# EbookReader_Schematic_11042025_v1.net
KiCad netlist of a schematic drawn in EAGLE
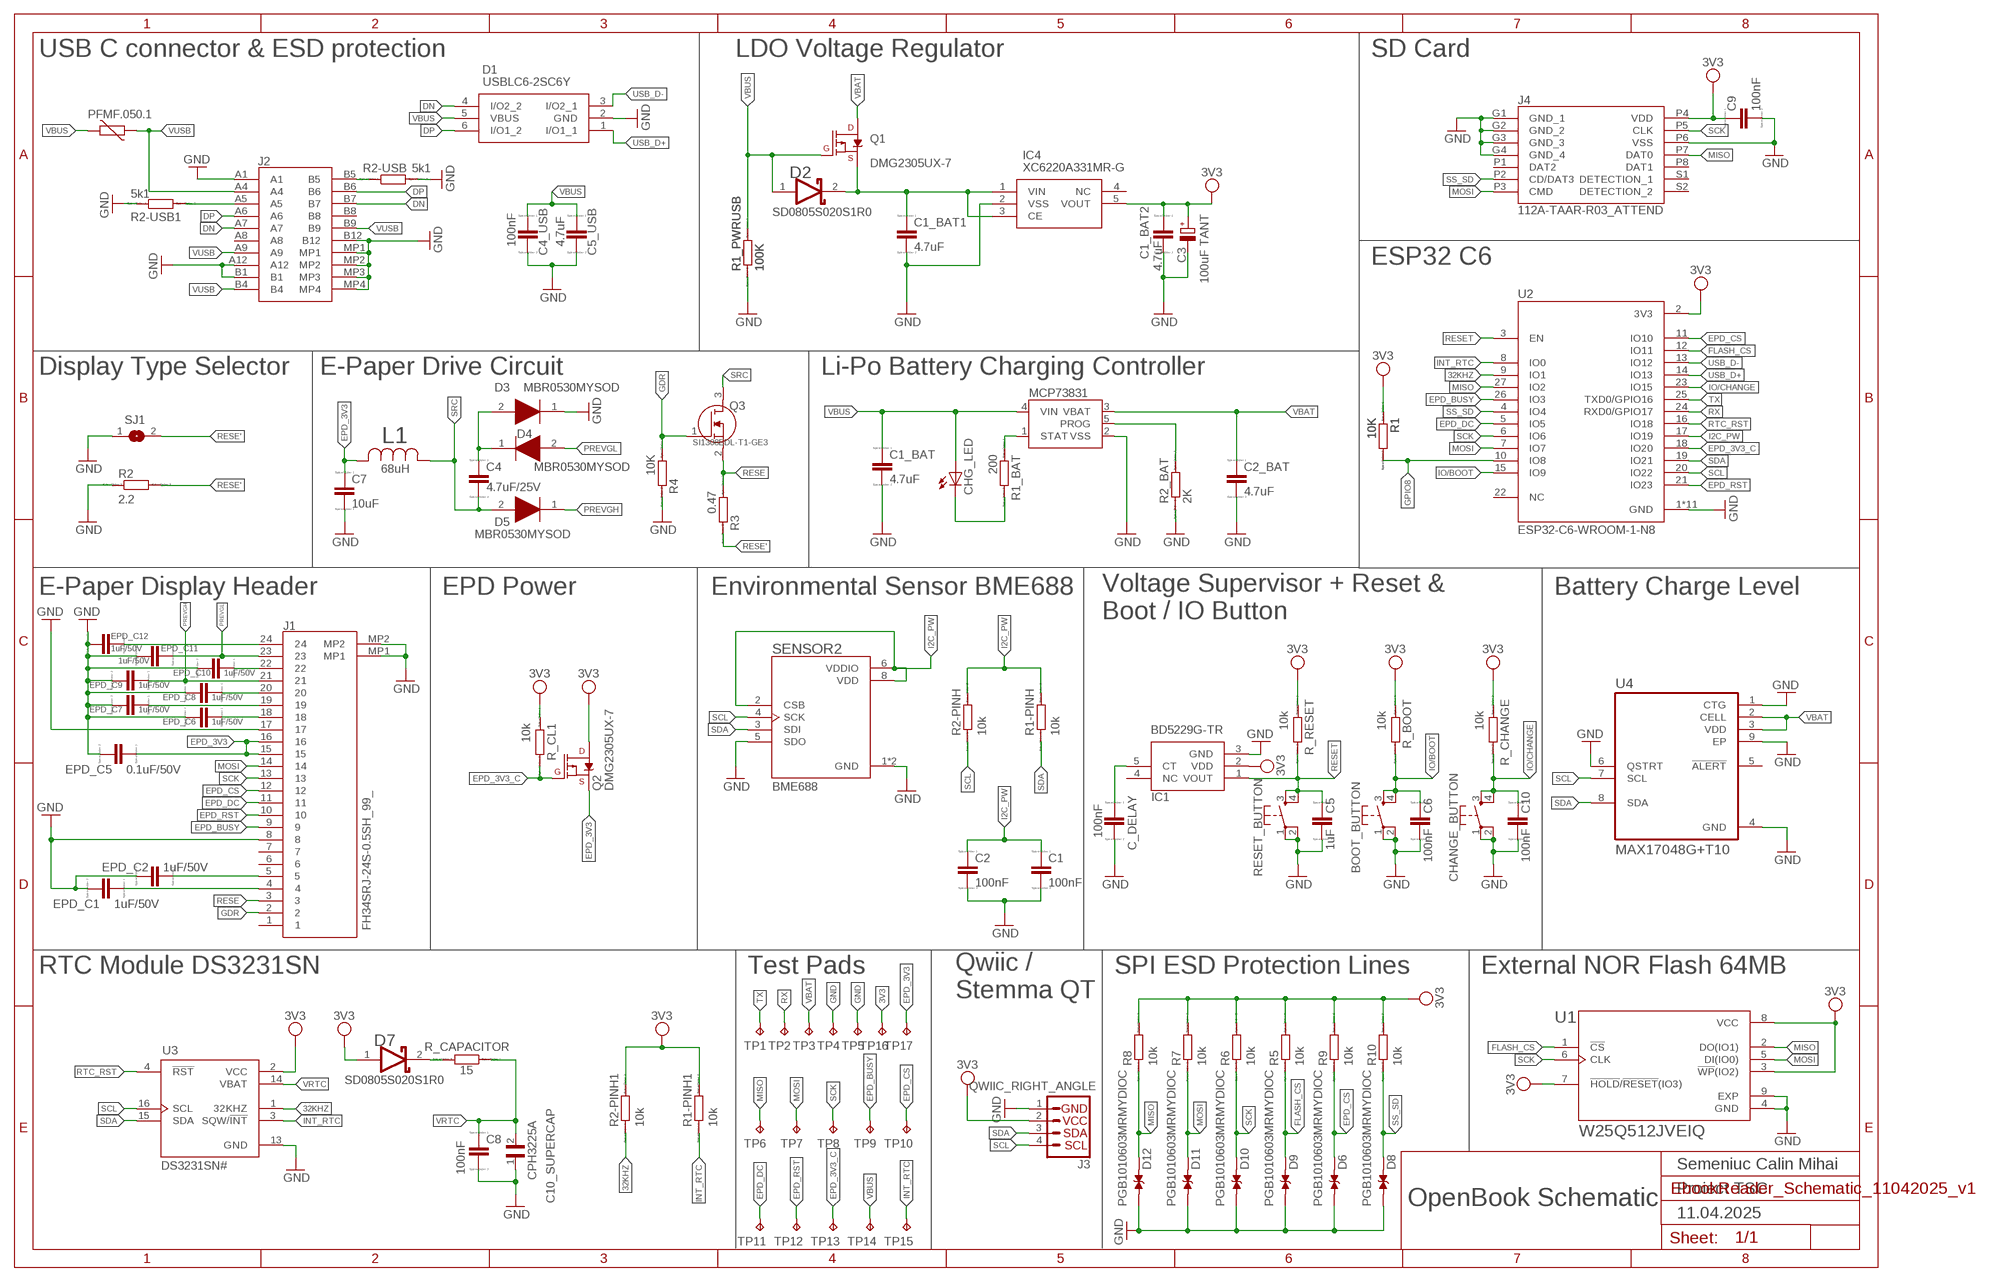
[diagram p0: schematic, sheet 1]

(export (version "E")
  (design (tool "Eeschema 10.0.6"))
  (components
    (comp (ref "BOOT_BUTTON")
      (value "BUTTON_CUSYOMV1FINAL_BUTT")
      (footprint "eagle-import:MYBUTTON")
      (libsource (lib "eagle-import") (part "BUTTON_CUSYOMV1FINAL_BUTT"))
    )
    (comp (ref "C1")
      (value "100nF")
      (footprint "eagle-import:EAGLE-LTSPICE_C0402")
      (libsource (lib "eagle-import") (part "ESP32_WROVER_EAGLE-LTSPICE_C"))
    )
    (comp (ref "C1_BAT")
      (value "4.7uF")
      (footprint "eagle-import:EAGLE-LTSPICE_C0402")
      (libsource (lib "eagle-import") (part "ESP32_WROVER_EAGLE-LTSPICE_C"))
    )
    (comp (ref "C1_BAT1")
      (value "4.7uF")
      (footprint "eagle-import:EAGLE-LTSPICE_C0402")
      (libsource (lib "eagle-import") (part "ESP32_WROVER_EAGLE-LTSPICE_C"))
    )
    (comp (ref "C1_BAT2")
      (value "4.7uF")
      (footprint "eagle-import:EAGLE-LTSPICE_C0402")
      (libsource (lib "eagle-import") (part "ESP32_WROVER_EAGLE-LTSPICE_C"))
    )
    (comp (ref "C2")
      (value "100nF")
      (footprint "eagle-import:EAGLE-LTSPICE_C0402")
      (libsource (lib "eagle-import") (part "ESP32_WROVER_EAGLE-LTSPICE_C"))
    )
    (comp (ref "C2_BAT")
      (value "4.7uF")
      (footprint "eagle-import:EAGLE-LTSPICE_C0402")
      (libsource (lib "eagle-import") (part "ESP32_WROVER_EAGLE-LTSPICE_C"))
    )
    (comp (ref "C3")
      (value "100uF TANT")
      (footprint "eagle-import:RCL_CT3528")
      (libsource (lib "eagle-import") (part "RCL_CPOL-EUCT3528"))
    )
    (comp (ref "C4")
      (value "4.7uF/25V")
      (footprint "eagle-import:EAGLE-LTSPICE_C0402")
      (libsource (lib "eagle-import") (part "ESP32_WROVER_EAGLE-LTSPICE_C"))
    )
    (comp (ref "C4_USB")
      (value "100nF")
      (footprint "eagle-import:EAGLE-LTSPICE_C0402")
      (libsource (lib "eagle-import") (part "ESP32_WROVER_EAGLE-LTSPICE_C"))
    )
    (comp (ref "C5")
      (value "1uF")
      (footprint "eagle-import:EAGLE-LTSPICE_C0402")
      (libsource (lib "eagle-import") (part "ESP32_WROVER_EAGLE-LTSPICE_C"))
    )
    (comp (ref "C5_USB")
      (value "4.7uF")
      (footprint "eagle-import:EAGLE-LTSPICE_C0402")
      (libsource (lib "eagle-import") (part "ESP32_WROVER_EAGLE-LTSPICE_C"))
    )
    (comp (ref "C6")
      (value "100nF")
      (footprint "eagle-import:EAGLE-LTSPICE_C0402")
      (libsource (lib "eagle-import") (part "ESP32_WROVER_EAGLE-LTSPICE_C"))
    )
    (comp (ref "C7")
      (value "10uF")
      (footprint "eagle-import:EAGLE-LTSPICE_C0402")
      (libsource (lib "eagle-import") (part "ESP32_WROVER_EAGLE-LTSPICE_C"))
    )
    (comp (ref "C8")
      (value "100nF")
      (footprint "eagle-import:EAGLE-LTSPICE_C0402")
      (libsource (lib "eagle-import") (part "ESP32_WROVER_EAGLE-LTSPICE_C"))
    )
    (comp (ref "C9")
      (value "100nF")
      (footprint "eagle-import:EAGLE-LTSPICE_C0402")
      (libsource (lib "eagle-import") (part "ESP32_WROVER_EAGLE-LTSPICE_C"))
    )
    (comp (ref "C10")
      (value "100nF")
      (footprint "eagle-import:EAGLE-LTSPICE_C0402")
      (libsource (lib "eagle-import") (part "ESP32_WROVER_EAGLE-LTSPICE_C"))
    )
    (comp (ref "C10_SUPERCAP")
      (value "CPH3225A")
      (footprint "eagle-import:CAPCP3225X100N")
      (fields (field (name "MF") "Seiko Instruments"))
      (libsource (lib "eagle-import") (part "CPH3225A"))
    )
    (comp (ref "CHANGE_BUTTON")
      (value "BUTTON_CUSYOMV1FINAL_BUTT")
      (footprint "eagle-import:MYBUTTON")
      (libsource (lib "eagle-import") (part "BUTTON_CUSYOMV1FINAL_BUTT"))
    )
    (comp (ref "CHG_LED")
      (value "ADAFRUIT_LEDCHIP-LED0603")
      (footprint "eagle-import:ADAFRUIT_CHIP-LED0603")
      (libsource (lib "eagle-import") (part "ADAFRUIT_LEDCHIP-LED0603"))
    )
    (comp (ref "C_DELAY")
      (value "100nF")
      (footprint "eagle-import:EAGLE-LTSPICE_C0402")
      (libsource (lib "eagle-import") (part "ESP32_WROVER_EAGLE-LTSPICE_C"))
    )
    (comp (ref "D1")
      (value "USBLC6-2SC6Y")
      (footprint "eagle-import:SOT95P280X145-6N")
      (fields (field (name "MF") "STMicroelectronics"))
      (libsource (lib "eagle-import") (part "USBLC6-2SC6Y"))
    )
    (comp (ref "D2")
      (value "ESP32_WROVER_AVX---SD0805S020S1R0_AVX_SD0805S020S1R0_0_0")
      (footprint "eagle-import:ESP32_WROVER_AVX---SD0805S020S1R0_AVX_SD0805S020S1R0_0")
      (fields (field (name "FOOPRINT") "SD0805S020S1R0"))
      (libsource (lib "eagle-import") (part "ESP32_WROVER_AVX---SD0805S020S1R0_AVX_SD0805S020S1R0_0_0"))
    )
    (comp (ref "D3")
      (value "MBR0530MYSOD")
      (footprint "eagle-import:SOD3716X135N")
      (libsource (lib "eagle-import") (part "MBR0530MYSOD"))
    )
    (comp (ref "D4")
      (value "MBR0530MYSOD")
      (footprint "eagle-import:SOD3716X135N")
      (libsource (lib "eagle-import") (part "MBR0530MYSOD"))
    )
    (comp (ref "D5")
      (value "MBR0530MYSOD")
      (footprint "eagle-import:SOD3716X135N")
      (libsource (lib "eagle-import") (part "MBR0530MYSOD"))
    )
    (comp (ref "D6")
      (value "PGB1010603MRMYDIOC")
      (footprint "eagle-import:DIOC1608X36N")
      (libsource (lib "eagle-import") (part "PGB1010603MRMYDIOC"))
    )
    (comp (ref "D7")
      (value "ESP32_WROVER_AVX---SD0805S020S1R0_AVX_SD0805S020S1R0_0_0")
      (footprint "eagle-import:ESP32_WROVER_AVX---SD0805S020S1R0_AVX_SD0805S020S1R0_0")
      (fields (field (name "FOOPRINT") "SD0805S020S1R0"))
      (libsource (lib "eagle-import") (part "ESP32_WROVER_AVX---SD0805S020S1R0_AVX_SD0805S020S1R0_0_0"))
    )
    (comp (ref "D8")
      (value "PGB1010603MRMYDIOC")
      (footprint "eagle-import:DIOC1608X36N")
      (libsource (lib "eagle-import") (part "PGB1010603MRMYDIOC"))
    )
    (comp (ref "D9")
      (value "PGB1010603MRMYDIOC")
      (footprint "eagle-import:DIOC1608X36N")
      (libsource (lib "eagle-import") (part "PGB1010603MRMYDIOC"))
    )
    (comp (ref "D10")
      (value "PGB1010603MRMYDIOC")
      (footprint "eagle-import:DIOC1608X36N")
      (libsource (lib "eagle-import") (part "PGB1010603MRMYDIOC"))
    )
    (comp (ref "D11")
      (value "PGB1010603MRMYDIOC")
      (footprint "eagle-import:DIOC1608X36N")
      (libsource (lib "eagle-import") (part "PGB1010603MRMYDIOC"))
    )
    (comp (ref "D12")
      (value "PGB1010603MRMYDIOC")
      (footprint "eagle-import:DIOC1608X36N")
      (libsource (lib "eagle-import") (part "PGB1010603MRMYDIOC"))
    )
    (comp (ref "EPD_C1")
      (value "1uF/50V")
      (footprint "eagle-import:EAGLE-LTSPICE_C0402")
      (libsource (lib "eagle-import") (part "ESP32_WROVER_EAGLE-LTSPICE_C"))
    )
    (comp (ref "EPD_C2")
      (value "1uF/50V")
      (footprint "eagle-import:EAGLE-LTSPICE_C0402")
      (libsource (lib "eagle-import") (part "ESP32_WROVER_EAGLE-LTSPICE_C"))
    )
    (comp (ref "EPD_C5")
      (value "0.1uF/50V")
      (footprint "eagle-import:EAGLE-LTSPICE_C0402")
      (libsource (lib "eagle-import") (part "ESP32_WROVER_EAGLE-LTSPICE_C"))
    )
    (comp (ref "EPD_C6")
      (value "1uF/50V")
      (footprint "eagle-import:EAGLE-LTSPICE_C0402")
      (libsource (lib "eagle-import") (part "ESP32_WROVER_EAGLE-LTSPICE_C"))
    )
    (comp (ref "EPD_C7")
      (value "1uF/50V")
      (footprint "eagle-import:EAGLE-LTSPICE_C0402")
      (libsource (lib "eagle-import") (part "ESP32_WROVER_EAGLE-LTSPICE_C"))
    )
    (comp (ref "EPD_C8")
      (value "1uF/50V")
      (footprint "eagle-import:EAGLE-LTSPICE_C0402")
      (libsource (lib "eagle-import") (part "ESP32_WROVER_EAGLE-LTSPICE_C"))
    )
    (comp (ref "EPD_C9")
      (value "1uF/50V")
      (footprint "eagle-import:EAGLE-LTSPICE_C0402")
      (libsource (lib "eagle-import") (part "ESP32_WROVER_EAGLE-LTSPICE_C"))
    )
    (comp (ref "EPD_C10")
      (value "1uF/50V")
      (footprint "eagle-import:EAGLE-LTSPICE_C0402")
      (libsource (lib "eagle-import") (part "ESP32_WROVER_EAGLE-LTSPICE_C"))
    )
    (comp (ref "EPD_C11")
      (value "1uF/50V")
      (footprint "eagle-import:EAGLE-LTSPICE_C0402")
      (libsource (lib "eagle-import") (part "ESP32_WROVER_EAGLE-LTSPICE_C"))
    )
    (comp (ref "EPD_C12")
      (value "1uF/50V")
      (footprint "eagle-import:EAGLE-LTSPICE_C0402")
      (libsource (lib "eagle-import") (part "ESP32_WROVER_EAGLE-LTSPICE_C"))
    )
    (comp (ref "IC1")
      (value "BD5229G-TR")
      (footprint "eagle-import:SOT95P280X125-5N")
      (fields (field (name "MOUSER_PART_NUMBER") "755-BD5229G-TR"))
      (libsource (lib "eagle-import") (part "BD5229G-TR"))
    )
    (comp (ref "IC4")
      (value "XC6220A331MR-G")
      (footprint "eagle-import:SOT95P280X120-5N")
      (fields (field (name "MOUSER_PART_NUMBER") "865-XC6220A331MR-G"))
      (libsource (lib "eagle-import") (part "XC6220A331MR-G"))
    )
    (comp (ref "J1")
      (value "FH34SRJ-24S-0.5SH_99_")
      (footprint "eagle-import:FH34SRJ24S05SH99")
      (fields
        (field (name "MANUFACTURER_PART_NUMBER") "FH34SRJ-24S-0.5SH(99)")
        (field (name "MOUSER_PART_NUMBER") "798-FH34SRJ24S05SH99")
      )
      (libsource (lib "eagle-import") (part "FH34SRJ-24S-0.5SH_99_"))
    )
    (comp (ref "J2")
      (value "SAMACSYS_PARTS_USB4110-GF-A")
      (footprint "eagle-import:SAMACSYS_PARTS_USB4110GFA")
      (fields
        (field (name "MANUFACTURER_PART_NUMBER") "USB4110-GF-A")
        (field (name "MOUSER_PART_NUMBER") "640-USB4110-GF-A")
      )
      (libsource (lib "eagle-import") (part "SAMACSYS_PARTS_USB4110-GF-A"))
    )
    (comp (ref "J3")
      (value "QWIIC_RIGHT_ANGLE")
      (footprint "eagle-import:JST04_1MM_RA")
      (libsource (lib "eagle-import") (part "QWIIC_CONNECTORJS-1MM"))
    )
    (comp (ref "J4")
      (value "112A-TAAR-R03_ATTEND")
      (footprint "eagle-import:112ATAARR03ATTEND")
      (fields (field (name "MANUFACTURER_PART_NUMBER") "112A-TAAR-R03 ATTEND"))
      (libsource (lib "eagle-import") (part "112A-TAAR-R03_ATTEND"))
    )
    (comp (ref "L1")
      (value "744043680IND_4828-WE-TPC_WRE")
      (footprint "eagle-import:IND_4828-WE-TPC_WRE")
      (fields
        (field (name "MANUFACTURER_PART_NUMBER") "744043680")
        (field (name "VAL") "68uH")
        (field (name "COPYRIGHT") "Copyright (C) 2024 Ultra Librarian. All rights reserved.")
      )
      (libsource (lib "eagle-import") (part "744043680IND_4828-WE-TPC_WRE"))
    )
    (comp (ref "MCP73831")
      (value "ESP32_WROVER_SPARKFUN-IC-POWER_MCP73831")
      (footprint "eagle-import:ESP32_WROVER_SPARKFUN-IC-POWER_SOT23-5")
      (libsource (lib "eagle-import") (part "ESP32_WROVER_SPARKFUN-IC-POWER_MCP73831"))
    )
    (comp (ref "PFMF.050.1")
      (value "ESP32C6_VARISTORCN1812")
      (footprint "eagle-import:ESP32C6_VARISTOR_CT_CN1812")
      (libsource (lib "eagle-import") (part "ESP32C6_VARISTORCN1812"))
    )
    (comp (ref "Q1")
      (value "20V/4.2A/52mΩ/1.4W")
      (footprint "DMG2305UX-7")
      (libsource (lib "eagle-import") (part "ESP32_WROVER_SPARKFUN-DISCRETESEMI_MOSFET_PCH"))
    )
    (comp (ref "Q2")
      (value "20V/4.2A/52mΩ/1.4W")
      (footprint "DMG2305UX-7")
      (libsource (lib "eagle-import") (part "ESP32_WROVER_SPARKFUN-DISCRETESEMI_MOSFET_PCH"))
    )
    (comp (ref "Q3")
      (value "SI1308EDL-T1-GE3")
      (footprint "eagle-import:SOT65P210X110-3N")
      (fields (field (name "MF") "Vishay Siliconix"))
      (libsource (lib "eagle-import") (part "SI1308EDL-T1-GE3"))
    )
    (comp (ref "R1")
      (value "10K")
      (footprint "eagle-import:ESP32_WROVER_EAGLE-LTSPICE_R0402")
      (libsource (lib "eagle-import") (part "ESP32_WROVER_EAGLE-LTSPICE_R"))
    )
    (comp (ref "R1-PINH")
      (value "10k")
      (footprint "eagle-import:ESP32_WROVER_EAGLE-LTSPICE_R0402")
      (libsource (lib "eagle-import") (part "ESP32_WROVER_EAGLE-LTSPICE_R"))
    )
    (comp (ref "R1-PINH1")
      (value "10k")
      (footprint "eagle-import:ESP32_WROVER_EAGLE-LTSPICE_R0402")
      (libsource (lib "eagle-import") (part "ESP32_WROVER_EAGLE-LTSPICE_R"))
    )
    (comp (ref "R1_BAT")
      (value "200")
      (footprint "eagle-import:ESP32_WROVER_EAGLE-LTSPICE_R0402")
      (libsource (lib "eagle-import") (part "ESP32_WROVER_EAGLE-LTSPICE_R"))
    )
    (comp (ref "R1_PWRUSB")
      (value "100K")
      (footprint "eagle-import:ESP32_WROVER_EAGLE-LTSPICE_R0402")
      (libsource (lib "eagle-import") (part "ESP32_WROVER_EAGLE-LTSPICE_R"))
    )
    (comp (ref "R2")
      (value "2.2")
      (footprint "eagle-import:ESP32_WROVER_EAGLE-LTSPICE_R0402")
      (libsource (lib "eagle-import") (part "ESP32_WROVER_EAGLE-LTSPICE_R"))
    )
    (comp (ref "R2-PINH")
      (value "10k")
      (footprint "eagle-import:ESP32_WROVER_EAGLE-LTSPICE_R0402")
      (libsource (lib "eagle-import") (part "ESP32_WROVER_EAGLE-LTSPICE_R"))
    )
    (comp (ref "R2-PINH1")
      (value "10k")
      (footprint "eagle-import:ESP32_WROVER_EAGLE-LTSPICE_R0402")
      (libsource (lib "eagle-import") (part "ESP32_WROVER_EAGLE-LTSPICE_R"))
    )
    (comp (ref "R2-USB")
      (value "5k1")
      (footprint "eagle-import:ESP32_WROVER_EAGLE-LTSPICE_R0402")
      (libsource (lib "eagle-import") (part "ESP32_WROVER_EAGLE-LTSPICE_R"))
    )
    (comp (ref "R2-USB1")
      (value "5k1")
      (footprint "eagle-import:ESP32_WROVER_EAGLE-LTSPICE_R0402")
      (libsource (lib "eagle-import") (part "ESP32_WROVER_EAGLE-LTSPICE_R"))
    )
    (comp (ref "R2_BAT")
      (value "2K")
      (footprint "eagle-import:ESP32_WROVER_EAGLE-LTSPICE_R0402")
      (libsource (lib "eagle-import") (part "ESP32_WROVER_EAGLE-LTSPICE_R"))
    )
    (comp (ref "R3")
      (value "0.47")
      (footprint "eagle-import:ESP32_WROVER_EAGLE-LTSPICE_R0402")
      (libsource (lib "eagle-import") (part "ESP32_WROVER_EAGLE-LTSPICE_R"))
    )
    (comp (ref "R4")
      (value "10K")
      (footprint "eagle-import:ESP32_WROVER_EAGLE-LTSPICE_R0402")
      (libsource (lib "eagle-import") (part "ESP32_WROVER_EAGLE-LTSPICE_R"))
    )
    (comp (ref "R5")
      (value "10k")
      (footprint "eagle-import:ESP32_WROVER_EAGLE-LTSPICE_R0402")
      (libsource (lib "eagle-import") (part "ESP32_WROVER_EAGLE-LTSPICE_R"))
    )
    (comp (ref "R6")
      (value "10k")
      (footprint "eagle-import:ESP32_WROVER_EAGLE-LTSPICE_R0402")
      (libsource (lib "eagle-import") (part "ESP32_WROVER_EAGLE-LTSPICE_R"))
    )
    (comp (ref "R7")
      (value "10k")
      (footprint "eagle-import:ESP32_WROVER_EAGLE-LTSPICE_R0402")
      (libsource (lib "eagle-import") (part "ESP32_WROVER_EAGLE-LTSPICE_R"))
    )
    (comp (ref "R8")
      (value "10k")
      (footprint "eagle-import:ESP32_WROVER_EAGLE-LTSPICE_R0402")
      (libsource (lib "eagle-import") (part "ESP32_WROVER_EAGLE-LTSPICE_R"))
    )
    (comp (ref "R9")
      (value "10k")
      (footprint "eagle-import:ESP32_WROVER_EAGLE-LTSPICE_R0402")
      (libsource (lib "eagle-import") (part "ESP32_WROVER_EAGLE-LTSPICE_R"))
    )
    (comp (ref "R10")
      (value "10k")
      (footprint "eagle-import:ESP32_WROVER_EAGLE-LTSPICE_R0402")
      (libsource (lib "eagle-import") (part "ESP32_WROVER_EAGLE-LTSPICE_R"))
    )
    (comp (ref "RESET_BUTTON")
      (value "BUTTON_CUSYOMV1FINAL_BUTT")
      (footprint "eagle-import:MYBUTTON")
      (libsource (lib "eagle-import") (part "BUTTON_CUSYOMV1FINAL_BUTT"))
    )
    (comp (ref "R_BOOT")
      (value "10k")
      (footprint "eagle-import:ESP32_WROVER_EAGLE-LTSPICE_R0402")
      (libsource (lib "eagle-import") (part "ESP32_WROVER_EAGLE-LTSPICE_R"))
    )
    (comp (ref "R_CAPACITOR")
      (value "15")
      (footprint "eagle-import:ESP32_WROVER_EAGLE-LTSPICE_R0402")
      (libsource (lib "eagle-import") (part "ESP32_WROVER_EAGLE-LTSPICE_R"))
    )
    (comp (ref "R_CHANGE")
      (value "10k")
      (footprint "eagle-import:ESP32_WROVER_EAGLE-LTSPICE_R0402")
      (libsource (lib "eagle-import") (part "ESP32_WROVER_EAGLE-LTSPICE_R"))
    )
    (comp (ref "R_CL1")
      (value "10k")
      (footprint "eagle-import:ESP32_WROVER_EAGLE-LTSPICE_R0402")
      (libsource (lib "eagle-import") (part "ESP32_WROVER_EAGLE-LTSPICE_R"))
    )
    (comp (ref "R_RESET")
      (value "10k")
      (footprint "eagle-import:ESP32_WROVER_EAGLE-LTSPICE_R0402")
      (libsource (lib "eagle-import") (part "ESP32_WROVER_EAGLE-LTSPICE_R"))
    )
    (comp (ref "SENSOR2")
      (value "ESP32_WROVER_BME680_BME680")
      (footprint "BME688")
      (fields (field (name "MF") "Bosch Sensortec") (field (name "MP") "BME680"))
      (libsource (lib "eagle-import") (part "ESP32_WROVER_BME680_BME680"))
    )
    (comp (ref "SJ1") (value "SJ") (footprint "eagle-import:SJ") (libsource (lib "eagle-import") (part "SJ")))
    (comp (ref "TP1")
      (value "TP")
      (footprint "eagle-import:TP20R")
      (libsource (lib "eagle-import") (part "TP"))
    )
    (comp (ref "TP2")
      (value "TP")
      (footprint "eagle-import:TP20R")
      (libsource (lib "eagle-import") (part "TP"))
    )
    (comp (ref "TP3")
      (value "TP")
      (footprint "eagle-import:TP20R")
      (libsource (lib "eagle-import") (part "TP"))
    )
    (comp (ref "TP4")
      (value "TP")
      (footprint "eagle-import:TP20R")
      (libsource (lib "eagle-import") (part "TP"))
    )
    (comp (ref "TP5")
      (value "TP")
      (footprint "eagle-import:TP20R")
      (libsource (lib "eagle-import") (part "TP"))
    )
    (comp (ref "TP6")
      (value "TP")
      (footprint "eagle-import:TP20R")
      (libsource (lib "eagle-import") (part "TP"))
    )
    (comp (ref "TP7")
      (value "TP")
      (footprint "eagle-import:TP20R")
      (libsource (lib "eagle-import") (part "TP"))
    )
    (comp (ref "TP8")
      (value "TP")
      (footprint "eagle-import:TP20R")
      (libsource (lib "eagle-import") (part "TP"))
    )
    (comp (ref "TP9")
      (value "TP")
      (footprint "eagle-import:TP20R")
      (libsource (lib "eagle-import") (part "TP"))
    )
    (comp (ref "TP10")
      (value "TP")
      (footprint "eagle-import:TP20R")
      (libsource (lib "eagle-import") (part "TP"))
    )
    (comp (ref "TP11")
      (value "TP")
      (footprint "eagle-import:TP20R")
      (libsource (lib "eagle-import") (part "TP"))
    )
    (comp (ref "TP12")
      (value "TP")
      (footprint "eagle-import:TP20R")
      (libsource (lib "eagle-import") (part "TP"))
    )
    (comp (ref "TP13")
      (value "TP")
      (footprint "eagle-import:TP20R")
      (libsource (lib "eagle-import") (part "TP"))
    )
    (comp (ref "TP14")
      (value "TP")
      (footprint "eagle-import:TP20R")
      (libsource (lib "eagle-import") (part "TP"))
    )
    (comp (ref "TP15")
      (value "TP")
      (footprint "eagle-import:TP20R")
      (libsource (lib "eagle-import") (part "TP"))
    )
    (comp (ref "TP16")
      (value "TP")
      (footprint "eagle-import:TP20R")
      (libsource (lib "eagle-import") (part "TP"))
    )
    (comp (ref "TP17")
      (value "TP")
      (footprint "eagle-import:TP20R")
      (libsource (lib "eagle-import") (part "TP"))
    )
    (comp (ref "U1")
      (value "W25Q512JVEIQ")
      (footprint "eagle-import:SON127P600X800X80-9N")
      (fields (field (name "MF") "Winbond Electronics"))
      (libsource (lib "eagle-import") (part "W25Q512JVEIQ"))
    )
    (comp (ref "U2")
      (value "ESP32-C6-WROOM-1-N8")
      (footprint "eagle-import:XCVR_ESP32-C6-WROOM-1-N8")
      (fields (field (name "MF") "Espressif Systems"))
      (libsource (lib "eagle-import") (part "ESP32-C6-WROOM-1-N8"))
    )
    (comp (ref "U3")
      (value "DS3231SN#")
      (footprint "eagle-import:SOIC127P1032X265-16N")
      (fields (field (name "MF") "Analog Devices"))
      (libsource (lib "eagle-import") (part "DS3231SN#"))
    )
    (comp (ref "U4")
      (value "MAX17048G+T10")
      (footprint "eagle-import:SON50P200X200X80-9N")
      (fields (field (name "MF") "Analog Devices") (field (name "SPICEPREFIX") "X"))
      (libsource (lib "eagle-import") (part "MAX17048G+T10"))
    )
  )
  (nets
    (net (code "1") (name "3V3") (class "Default")
      (node (ref "C1_BAT2") (pin "1") (pinfunction "1_1") (pintype "passive"))
      (node (ref "C3") (pin "+") (pinfunction "+_+") (pintype "passive"))
      (node (ref "C9") (pin "1") (pinfunction "1_1") (pintype "passive"))
      (node (ref "D7") (pin "1") (pinfunction "ANODE_1") (pintype "bidirectional"))
      (node (ref "IC1") (pin "2") (pinfunction "VDD_2") (pintype "bidirectional"))
      (node (ref "IC4") (pin "5") (pinfunction "VOUT_5") (pintype "bidirectional"))
      (node (ref "J3") (pin "2") (pinfunction "2_2") (pintype "power_in"))
      (node (ref "J4") (pin "P4") (pinfunction "VDD_P4") (pintype "bidirectional"))
      (node (ref "Q2") (pin "1") (pinfunction "D_1") (pintype "bidirectional"))
      (node (ref "R1") (pin "1") (pinfunction "1_1") (pintype "passive"))
      (node (ref "R1-PINH1") (pin "2") (pinfunction "2_2") (pintype "passive"))
      (node (ref "R10") (pin "2") (pinfunction "2_2") (pintype "passive"))
      (node (ref "R2-PINH1") (pin "2") (pinfunction "2_2") (pintype "passive"))
      (node (ref "R5") (pin "2") (pinfunction "2_2") (pintype "passive"))
      (node (ref "R6") (pin "2") (pinfunction "2_2") (pintype "passive"))
      (node (ref "R7") (pin "2") (pinfunction "2_2") (pintype "passive"))
      (node (ref "R8") (pin "2") (pinfunction "2_2") (pintype "passive"))
      (node (ref "R9") (pin "2") (pinfunction "2_2") (pintype "passive"))
      (node (ref "R_BOOT") (pin "1") (pinfunction "1_1") (pintype "passive"))
      (node (ref "R_CHANGE") (pin "1") (pinfunction "1_1") (pintype "passive"))
      (node (ref "R_CL1") (pin "1") (pinfunction "1_1") (pintype "passive"))
      (node (ref "R_RESET") (pin "1") (pinfunction "1_1") (pintype "passive"))
      (node (ref "TP16") (pin "TP") (pinfunction "TP_TP") (pintype "input"))
      (node (ref "U1") (pin "3") (pinfunction "~{WP}(IO2)_3") (pintype "bidirectional"))
      (node (ref "U1") (pin "7") (pinfunction "~{HOLD}/~{RESET}(IO3)_7") (pintype "bidirectional"))
      (node (ref "U1") (pin "8") (pinfunction "VCC_8") (pintype "power_in"))
      (node (ref "U2") (pin "2") (pinfunction "3V3_2") (pintype "power_in"))
      (node (ref "U3") (pin "2") (pinfunction "VCC_2") (pintype "power_in"))
    )
    (net (code "2") (name "32KHZ") (class "Default")
      (node (ref "R2-PINH1") (pin "1") (pinfunction "1_1") (pintype "passive"))
      (node (ref "U2") (pin "9") (pinfunction "IO1_9") (pintype "bidirectional"))
      (node (ref "U3") (pin "1") (pinfunction "32KHZ_1") (pintype "output"))
    )
    (net (code "3") (name "DN") (class "Default")
      (node (ref "D1") (pin "4") (pinfunction "I/O2_2_4") (pintype "bidirectional"))
      (node (ref "J2") (pin "A7") (pinfunction "A7_A7") (pintype "bidirectional"))
      (node (ref "J2") (pin "B7") (pinfunction "B7_B7") (pintype "bidirectional"))
    )
    (net (code "4") (name "DP") (class "Default")
      (node (ref "D1") (pin "6") (pinfunction "I/O1_2_6") (pintype "bidirectional"))
      (node (ref "J2") (pin "A6") (pinfunction "A6_A6") (pintype "bidirectional"))
      (node (ref "J2") (pin "B6") (pinfunction "B6_B6") (pintype "bidirectional"))
    )
    (net (code "5") (name "EPD_3V3") (class "Default")
      (node (ref "C7") (pin "1") (pinfunction "1_1") (pintype "passive"))
      (node (ref "EPD_C5") (pin "1") (pinfunction "1_1") (pintype "passive"))
      (node (ref "J1") (pin "15") (pinfunction "15_15") (pintype "bidirectional"))
      (node (ref "J1") (pin "16") (pinfunction "16_16") (pintype "bidirectional"))
      (node (ref "L1") (pin "2") (pinfunction "2_2") (pintype "passive"))
      (node (ref "Q2") (pin "3") (pinfunction "S_3") (pintype "bidirectional"))
      (node (ref "TP17") (pin "TP") (pinfunction "TP_TP") (pintype "input"))
    )
    (net (code "6") (name "EPD_3V3_C") (class "Default")
      (node (ref "Q2") (pin "2") (pinfunction "G_2") (pintype "bidirectional"))
      (node (ref "R_CL1") (pin "2") (pinfunction "2_2") (pintype "passive"))
      (node (ref "TP13") (pin "TP") (pinfunction "TP_TP") (pintype "input"))
      (node (ref "U2") (pin "18") (pinfunction "IO20_18") (pintype "bidirectional"))
    )
    (net (code "7") (name "EPD_BUSY") (class "Default")
      (node (ref "J1") (pin "9") (pinfunction "9_9") (pintype "bidirectional"))
      (node (ref "TP9") (pin "TP") (pinfunction "TP_TP") (pintype "input"))
      (node (ref "U2") (pin "26") (pinfunction "IO3_26") (pintype "bidirectional"))
    )
    (net (code "8") (name "EPD_CS") (class "Default")
      (node (ref "D6") (pin "2") (pinfunction "2_2") (pintype "passive"))
      (node (ref "J1") (pin "12") (pinfunction "12_12") (pintype "bidirectional"))
      (node (ref "R9") (pin "1") (pinfunction "1_1") (pintype "passive"))
      (node (ref "TP10") (pin "TP") (pinfunction "TP_TP") (pintype "input"))
      (node (ref "U2") (pin "11") (pinfunction "IO10_11") (pintype "bidirectional"))
    )
    (net (code "9") (name "EPD_DC") (class "Default")
      (node (ref "J1") (pin "11") (pinfunction "11_11") (pintype "bidirectional"))
      (node (ref "TP11") (pin "TP") (pinfunction "TP_TP") (pintype "input"))
      (node (ref "U2") (pin "5") (pinfunction "IO5_5") (pintype "bidirectional"))
    )
    (net (code "10") (name "EPD_RST") (class "Default")
      (node (ref "J1") (pin "10") (pinfunction "10_10") (pintype "bidirectional"))
      (node (ref "TP12") (pin "TP") (pinfunction "TP_TP") (pintype "input"))
      (node (ref "U2") (pin "21") (pinfunction "IO23_21") (pintype "bidirectional"))
    )
    (net (code "11") (name "FLASH_CS") (class "Default")
      (node (ref "D9") (pin "2") (pinfunction "2_2") (pintype "passive"))
      (node (ref "R5") (pin "1") (pinfunction "1_1") (pintype "passive"))
      (node (ref "U1") (pin "1") (pinfunction "~{CS}_1") (pintype "input"))
      (node (ref "U2") (pin "12") (pinfunction "IO11_12") (pintype "bidirectional"))
    )
    (net (code "12") (name "GDR") (class "Default")
      (node (ref "J1") (pin "2") (pinfunction "2_2") (pintype "bidirectional"))
      (node (ref "Q3") (pin "1") (pinfunction "G_1") (pintype "bidirectional"))
      (node (ref "R4") (pin "1") (pinfunction "1_1") (pintype "passive"))
    )
    (net (code "13") (name "GND") (class "Default")
      (node (ref "BOOT_BUTTON") (pin "1") (pinfunction "1_1") (pintype "passive"))
      (node (ref "BOOT_BUTTON") (pin "2") (pinfunction "2_2") (pintype "passive"))
      (node (ref "C1") (pin "2") (pinfunction "2_2") (pintype "passive"))
      (node (ref "C10") (pin "2") (pinfunction "2_2") (pintype "passive"))
      (node (ref "C10_SUPERCAP") (pin "1") (pinfunction "1_1") (pintype "passive"))
      (node (ref "C1_BAT") (pin "2") (pinfunction "2_2") (pintype "passive"))
      (node (ref "C1_BAT1") (pin "2") (pinfunction "2_2") (pintype "passive"))
      (node (ref "C1_BAT2") (pin "2") (pinfunction "2_2") (pintype "passive"))
      (node (ref "C2") (pin "2") (pinfunction "2_2") (pintype "passive"))
      (node (ref "C2_BAT") (pin "2") (pinfunction "2_2") (pintype "passive"))
      (node (ref "C3") (pin "-") (pinfunction "-_-") (pintype "passive"))
      (node (ref "C4_USB") (pin "2") (pinfunction "2_2") (pintype "passive"))
      (node (ref "C5") (pin "2") (pinfunction "2_2") (pintype "passive"))
      (node (ref "C5_USB") (pin "2") (pinfunction "2_2") (pintype "passive"))
      (node (ref "C6") (pin "2") (pinfunction "2_2") (pintype "passive"))
      (node (ref "C7") (pin "2") (pinfunction "2_2") (pintype "passive"))
      (node (ref "C8") (pin "2") (pinfunction "2_2") (pintype "passive"))
      (node (ref "C9") (pin "2") (pinfunction "2_2") (pintype "passive"))
      (node (ref "CHANGE_BUTTON") (pin "1") (pinfunction "1_1") (pintype "passive"))
      (node (ref "CHANGE_BUTTON") (pin "2") (pinfunction "2_2") (pintype "passive"))
      (node (ref "C_DELAY") (pin "2") (pinfunction "2_2") (pintype "passive"))
      (node (ref "D1") (pin "2") (pinfunction "GND_2") (pintype "bidirectional"))
      (node (ref "D10") (pin "1") (pinfunction "1_1") (pintype "passive"))
      (node (ref "D11") (pin "1") (pinfunction "1_1") (pintype "passive"))
      (node (ref "D12") (pin "1") (pinfunction "1_1") (pintype "passive"))
      (node (ref "D3") (pin "1") (pinfunction "K_1") (pintype "bidirectional"))
      (node (ref "D6") (pin "1") (pinfunction "1_1") (pintype "passive"))
      (node (ref "D8") (pin "1") (pinfunction "1_1") (pintype "passive"))
      (node (ref "D9") (pin "1") (pinfunction "1_1") (pintype "passive"))
      (node (ref "EPD_C1") (pin "2") (pinfunction "2_2") (pintype "passive"))
      (node (ref "EPD_C10") (pin "2") (pinfunction "2_2") (pintype "passive"))
      (node (ref "EPD_C11") (pin "2") (pinfunction "2_2") (pintype "passive"))
      (node (ref "EPD_C12") (pin "2") (pinfunction "2_2") (pintype "passive"))
      (node (ref "EPD_C2") (pin "2") (pinfunction "2_2") (pintype "passive"))
      (node (ref "EPD_C5") (pin "2") (pinfunction "2_2") (pintype "passive"))
      (node (ref "EPD_C6") (pin "2") (pinfunction "2_2") (pintype "passive"))
      (node (ref "EPD_C7") (pin "2") (pinfunction "2_2") (pintype "passive"))
      (node (ref "EPD_C8") (pin "2") (pinfunction "2_2") (pintype "passive"))
      (node (ref "EPD_C9") (pin "2") (pinfunction "2_2") (pintype "passive"))
      (node (ref "IC1") (pin "3") (pinfunction "GND_3") (pintype "bidirectional"))
      (node (ref "IC4") (pin "2") (pinfunction "VSS_2") (pintype "bidirectional"))
      (node (ref "J1") (pin "17") (pinfunction "17_17") (pintype "bidirectional"))
      (node (ref "J1") (pin "8") (pinfunction "8_8") (pintype "bidirectional"))
      (node (ref "J1") (pin "MP1") (pinfunction "MP1_MP1") (pintype "bidirectional"))
      (node (ref "J1") (pin "MP2") (pinfunction "MP2_MP2") (pintype "bidirectional"))
      (node (ref "J2") (pin "A1") (pinfunction "A1_A1") (pintype "bidirectional"))
      (node (ref "J2") (pin "A12") (pinfunction "A12_A12") (pintype "bidirectional"))
      (node (ref "J2") (pin "B1") (pinfunction "B1_B1") (pintype "bidirectional"))
      (node (ref "J2") (pin "B12") (pinfunction "B12_B12") (pintype "bidirectional"))
      (node (ref "J2") (pin "MP1") (pinfunction "MP1_MP1") (pintype "bidirectional"))
      (node (ref "J2") (pin "MP2") (pinfunction "MP2_MP2") (pintype "bidirectional"))
      (node (ref "J2") (pin "MP3") (pinfunction "MP3_MP3") (pintype "bidirectional"))
      (node (ref "J2") (pin "MP4") (pinfunction "MP4_MP4") (pintype "bidirectional"))
      (node (ref "J3") (pin "1") (pinfunction "1_1") (pintype "power_in"))
      (node (ref "J4") (pin "G1") (pinfunction "GND_1_G1") (pintype "bidirectional"))
      (node (ref "J4") (pin "G2") (pinfunction "GND_2_G2") (pintype "bidirectional"))
      (node (ref "J4") (pin "G3") (pinfunction "GND_3_G3") (pintype "bidirectional"))
      (node (ref "J4") (pin "G4") (pinfunction "GND_4_G4") (pintype "bidirectional"))
      (node (ref "J4") (pin "P6") (pinfunction "VSS_P6") (pintype "bidirectional"))
      (node (ref "MCP73831") (pin "2") (pinfunction "VSS_2") (pintype "power_in"))
      (node (ref "R1_PWRUSB") (pin "1") (pinfunction "1_1") (pintype "passive"))
      (node (ref "R2") (pin "1") (pinfunction "1_1") (pintype "passive"))
      (node (ref "R2-USB") (pin "2") (pinfunction "2_2") (pintype "passive"))
      (node (ref "R2-USB1") (pin "1") (pinfunction "1_1") (pintype "passive"))
      (node (ref "R2_BAT") (pin "1") (pinfunction "1_1") (pintype "passive"))
      (node (ref "R4") (pin "2") (pinfunction "2_2") (pintype "passive"))
      (node (ref "RESET_BUTTON") (pin "1") (pinfunction "1_1") (pintype "passive"))
      (node (ref "RESET_BUTTON") (pin "2") (pinfunction "2_2") (pintype "passive"))
      (node (ref "SENSOR2") (pin "1") (pinfunction "GND_1") (pintype "power_in"))
      (node (ref "SENSOR2") (pin "5") (pinfunction "SDO_5") (pintype "bidirectional"))
      (node (ref "SENSOR2") (pin "7") (pinfunction "GND_7") (pintype "power_in"))
      (node (ref "SJ1") (pin "1") (pinfunction "1_1") (pintype "passive"))
      (node (ref "TP4") (pin "TP") (pinfunction "TP_TP") (pintype "input"))
      (node (ref "TP5") (pin "TP") (pinfunction "TP_TP") (pintype "input"))
      (node (ref "U1") (pin "4") (pinfunction "GND_4") (pintype "power_in"))
      (node (ref "U1") (pin "9") (pinfunction "EXP_9") (pintype "passive"))
      (node (ref "U2") (pin "1") (pinfunction "GND_1") (pintype "power_in"))
      (node (ref "U2") (pin "28") (pinfunction "GND_28") (pintype "power_in"))
      (node (ref "U2") (pin "29_1") (pinfunction "GND_29_1") (pintype "power_in"))
      (node (ref "U2") (pin "29_2") (pinfunction "GND_29_2") (pintype "power_in"))
      (node (ref "U2") (pin "29_3") (pinfunction "GND_29_3") (pintype "power_in"))
      (node (ref "U2") (pin "29_4") (pinfunction "GND_29_4") (pintype "power_in"))
      (node (ref "U2") (pin "29_5") (pinfunction "GND_29_5") (pintype "power_in"))
      (node (ref "U2") (pin "29_6") (pinfunction "GND_29_6") (pintype "power_in"))
      (node (ref "U2") (pin "29_7") (pinfunction "GND_29_7") (pintype "power_in"))
      (node (ref "U2") (pin "29_8") (pinfunction "GND_29_8") (pintype "power_in"))
      (node (ref "U2") (pin "29_9") (pinfunction "GND_29_9") (pintype "power_in"))
      (node (ref "U3") (pin "13") (pinfunction "GND_13") (pintype "power_in"))
      (node (ref "U4") (pin "1") (pinfunction "CTG_1") (pintype "power_in"))
      (node (ref "U4") (pin "4") (pinfunction "GND_4") (pintype "power_in"))
      (node (ref "U4") (pin "6") (pinfunction "QSTRT_6") (pintype "input"))
      (node (ref "U4") (pin "9") (pinfunction "EP_9") (pintype "power_in"))
    )
    (net (code "14") (name "GPIO8") (class "Default")
      (node (ref "R1") (pin "2") (pinfunction "2_2") (pintype "passive"))
      (node (ref "U2") (pin "10") (pinfunction "IO8_10") (pintype "bidirectional"))
    )
    (net (code "15") (name "I2C_PW") (class "Default")
      (node (ref "C1") (pin "1") (pinfunction "1_1") (pintype "passive"))
      (node (ref "C2") (pin "1") (pinfunction "1_1") (pintype "passive"))
      (node (ref "R1-PINH") (pin "2") (pinfunction "2_2") (pintype "passive"))
      (node (ref "R2-PINH") (pin "2") (pinfunction "2_2") (pintype "passive"))
      (node (ref "SENSOR2") (pin "2") (pinfunction "CSB_2") (pintype "input"))
      (node (ref "SENSOR2") (pin "6") (pinfunction "VDDIO_6") (pintype "power_in"))
      (node (ref "SENSOR2") (pin "8") (pinfunction "VDD_8") (pintype "power_in"))
      (node (ref "U2") (pin "17") (pinfunction "IO19_17") (pintype "bidirectional"))
    )
    (net (code "16") (name "INT_RTC") (class "Default")
      (node (ref "R1-PINH1") (pin "1") (pinfunction "1_1") (pintype "passive"))
      (node (ref "TP15") (pin "TP") (pinfunction "TP_TP") (pintype "input"))
      (node (ref "U2") (pin "8") (pinfunction "IO0_8") (pintype "bidirectional"))
      (node (ref "U3") (pin "3") (pinfunction "SQW/~{INT}_3") (pintype "output"))
    )
    (net (code "17") (name "IO{slash}BOOT") (class "Default")
      (node (ref "BOOT_BUTTON") (pin "3") (pinfunction "3_3") (pintype "passive"))
      (node (ref "BOOT_BUTTON") (pin "4") (pinfunction "4_4") (pintype "passive"))
      (node (ref "C6") (pin "1") (pinfunction "1_1") (pintype "passive"))
      (node (ref "R_BOOT") (pin "2") (pinfunction "2_2") (pintype "passive"))
      (node (ref "U2") (pin "15") (pinfunction "IO9_15") (pintype "bidirectional"))
    )
    (net (code "18") (name "IO{slash}CHANGE") (class "Default")
      (node (ref "C10") (pin "1") (pinfunction "1_1") (pintype "passive"))
      (node (ref "CHANGE_BUTTON") (pin "3") (pinfunction "3_3") (pintype "passive"))
      (node (ref "CHANGE_BUTTON") (pin "4") (pinfunction "4_4") (pintype "passive"))
      (node (ref "R_CHANGE") (pin "2") (pinfunction "2_2") (pintype "passive"))
      (node (ref "U2") (pin "23") (pinfunction "IO15_23") (pintype "bidirectional"))
    )
    (net (code "19") (name "MISO") (class "Default")
      (node (ref "D12") (pin "2") (pinfunction "2_2") (pintype "passive"))
      (node (ref "J4") (pin "P7") (pinfunction "DAT0_P7") (pintype "bidirectional"))
      (node (ref "R8") (pin "1") (pinfunction "1_1") (pintype "passive"))
      (node (ref "TP6") (pin "TP") (pinfunction "TP_TP") (pintype "input"))
      (node (ref "U1") (pin "2") (pinfunction "DO(IO1)_2") (pintype "bidirectional"))
      (node (ref "U2") (pin "27") (pinfunction "IO2_27") (pintype "bidirectional"))
    )
    (net (code "20") (name "MOSI") (class "Default")
      (node (ref "D11") (pin "2") (pinfunction "2_2") (pintype "passive"))
      (node (ref "J1") (pin "14") (pinfunction "14_14") (pintype "bidirectional"))
      (node (ref "J4") (pin "P3") (pinfunction "CMD_P3") (pintype "bidirectional"))
      (node (ref "R7") (pin "1") (pinfunction "1_1") (pintype "passive"))
      (node (ref "TP7") (pin "TP") (pinfunction "TP_TP") (pintype "input"))
      (node (ref "U1") (pin "5") (pinfunction "DI(IO0)_5") (pintype "bidirectional"))
      (node (ref "U2") (pin "7") (pinfunction "IO7_7") (pintype "bidirectional"))
    )
    (net (code "21") (name "Net-(CHG_LED-PadC)") (class "Default")
      (node (ref "CHG_LED") (pin "C") (pinfunction "C_C") (pintype "passive"))
      (node (ref "R1_BAT") (pin "2") (pinfunction "2_2") (pintype "passive"))
    )
    (net (code "22") (name "Net-(D2-CATHODE)") (class "Default")
      (node (ref "C1_BAT1") (pin "1") (pinfunction "1_1") (pintype "passive"))
      (node (ref "D2") (pin "2") (pinfunction "CATHODE_2") (pintype "bidirectional"))
      (node (ref "IC4") (pin "1") (pinfunction "VIN_1") (pintype "bidirectional"))
      (node (ref "IC4") (pin "3") (pinfunction "CE_3") (pintype "bidirectional"))
      (node (ref "Q1") (pin "3") (pinfunction "S_3") (pintype "bidirectional"))
    )
    (net (code "23") (name "Net-(D3-A)") (class "Default")
      (node (ref "C4") (pin "1") (pinfunction "1_1") (pintype "passive"))
      (node (ref "D3") (pin "2") (pinfunction "A_2") (pintype "bidirectional"))
      (node (ref "D4") (pin "1") (pinfunction "K_1") (pintype "bidirectional"))
    )
    (net (code "24") (name "Net-(D7-CATHODE)") (class "Default")
      (node (ref "D7") (pin "2") (pinfunction "CATHODE_2") (pintype "bidirectional"))
      (node (ref "R_CAPACITOR") (pin "2") (pinfunction "2_2") (pintype "passive"))
    )
    (net (code "25") (name "Net-(EPD_C1-Pad1)") (class "Default")
      (node (ref "EPD_C1") (pin "1") (pinfunction "1_1") (pintype "passive"))
      (node (ref "J1") (pin "4") (pinfunction "4_4") (pintype "bidirectional"))
    )
    (net (code "26") (name "Net-(EPD_C2-Pad1)") (class "Default")
      (node (ref "EPD_C2") (pin "1") (pinfunction "1_1") (pintype "passive"))
      (node (ref "J1") (pin "5") (pinfunction "5_5") (pintype "bidirectional"))
    )
    (net (code "27") (name "Net-(EPD_C6-Pad1)") (class "Default")
      (node (ref "EPD_C6") (pin "1") (pinfunction "1_1") (pintype "passive"))
      (node (ref "J1") (pin "18") (pinfunction "18_18") (pintype "bidirectional"))
    )
    (net (code "28") (name "Net-(EPD_C7-Pad1)") (class "Default")
      (node (ref "EPD_C7") (pin "1") (pinfunction "1_1") (pintype "passive"))
      (node (ref "J1") (pin "19") (pinfunction "19_19") (pintype "bidirectional"))
    )
    (net (code "29") (name "Net-(EPD_C8-Pad1)") (class "Default")
      (node (ref "EPD_C8") (pin "1") (pinfunction "1_1") (pintype "passive"))
      (node (ref "J1") (pin "20") (pinfunction "20_20") (pintype "bidirectional"))
    )
    (net (code "30") (name "Net-(EPD_C10-Pad1)") (class "Default")
      (node (ref "EPD_C10") (pin "1") (pinfunction "1_1") (pintype "passive"))
      (node (ref "J1") (pin "22") (pinfunction "22_22") (pintype "bidirectional"))
    )
    (net (code "31") (name "Net-(EPD_C12-Pad1)") (class "Default")
      (node (ref "EPD_C12") (pin "1") (pinfunction "1_1") (pintype "passive"))
      (node (ref "J1") (pin "24") (pinfunction "24_24") (pintype "bidirectional"))
    )
    (net (code "32") (name "Net-(IC1-CT)") (class "Default")
      (node (ref "C_DELAY") (pin "1") (pinfunction "1_1") (pintype "passive"))
      (node (ref "IC1") (pin "5") (pinfunction "CT_5") (pintype "bidirectional"))
    )
    (net (code "33") (name "Net-(J2-PadA5)") (class "Default")
      (node (ref "J2") (pin "A5") (pinfunction "A5_A5") (pintype "bidirectional"))
      (node (ref "R2-USB1") (pin "2") (pinfunction "2_2") (pintype "passive"))
    )
    (net (code "34") (name "Net-(J2-PadB5)") (class "Default")
      (node (ref "J2") (pin "B5") (pinfunction "B5_B5") (pintype "bidirectional"))
      (node (ref "R2-USB") (pin "1") (pinfunction "1_1") (pintype "passive"))
    )
    (net (code "35") (name "Net-(MCP73831-PROG)") (class "Default")
      (node (ref "MCP73831") (pin "5") (pinfunction "PROG_5") (pintype "input"))
      (node (ref "R2_BAT") (pin "2") (pinfunction "2_2") (pintype "passive"))
    )
    (net (code "36") (name "Net-(MCP73831-STAT)") (class "Default")
      (node (ref "MCP73831") (pin "1") (pinfunction "STAT_1") (pintype "output"))
      (node (ref "R1_BAT") (pin "1") (pinfunction "1_1") (pintype "passive"))
    )
    (net (code "37") (name "PREVGH") (class "Default")
      (node (ref "D5") (pin "1") (pinfunction "K_1") (pintype "bidirectional"))
      (node (ref "EPD_C9") (pin "1") (pinfunction "1_1") (pintype "passive"))
      (node (ref "J1") (pin "21") (pinfunction "21_21") (pintype "bidirectional"))
    )
    (net (code "38") (name "PREVGL") (class "Default")
      (node (ref "D4") (pin "2") (pinfunction "A_2") (pintype "bidirectional"))
      (node (ref "EPD_C11") (pin "1") (pinfunction "1_1") (pintype "passive"))
      (node (ref "J1") (pin "23") (pinfunction "23_23") (pintype "bidirectional"))
    )
    (net (code "39") (name "RESE") (class "Default")
      (node (ref "J1") (pin "3") (pinfunction "3_3") (pintype "bidirectional"))
      (node (ref "Q3") (pin "2") (pinfunction "S_2") (pintype "bidirectional"))
      (node (ref "R3") (pin "1") (pinfunction "1_1") (pintype "passive"))
    )
    (net (code "40") (name "RESE'") (class "Default")
      (node (ref "R2") (pin "2") (pinfunction "2_2") (pintype "passive"))
      (node (ref "R3") (pin "2") (pinfunction "2_2") (pintype "passive"))
      (node (ref "SJ1") (pin "2") (pinfunction "2_2") (pintype "passive"))
    )
    (net (code "41") (name "RESET") (class "Default")
      (node (ref "C5") (pin "1") (pinfunction "1_1") (pintype "passive"))
      (node (ref "IC1") (pin "1") (pinfunction "VOUT_1") (pintype "bidirectional"))
      (node (ref "RESET_BUTTON") (pin "3") (pinfunction "3_3") (pintype "passive"))
      (node (ref "RESET_BUTTON") (pin "4") (pinfunction "4_4") (pintype "passive"))
      (node (ref "R_RESET") (pin "2") (pinfunction "2_2") (pintype "passive"))
      (node (ref "U2") (pin "3") (pinfunction "EN_3") (pintype "input"))
    )
    (net (code "42") (name "RTC_RST") (class "Default")
      (node (ref "U2") (pin "16") (pinfunction "IO18_16") (pintype "bidirectional"))
      (node (ref "U3") (pin "4") (pinfunction "~{RST}_4") (pintype "input"))
    )
    (net (code "43") (name "RX") (class "Default")
      (node (ref "TP2") (pin "TP") (pinfunction "TP_TP") (pintype "input"))
      (node (ref "U2") (pin "24") (pinfunction "RXD0/GPIO17_24") (pintype "bidirectional"))
    )
    (net (code "44") (name "SCK") (class "Default")
      (node (ref "D10") (pin "2") (pinfunction "2_2") (pintype "passive"))
      (node (ref "J1") (pin "13") (pinfunction "13_13") (pintype "bidirectional"))
      (node (ref "J4") (pin "P5") (pinfunction "CLK_P5") (pintype "bidirectional"))
      (node (ref "R6") (pin "1") (pinfunction "1_1") (pintype "passive"))
      (node (ref "TP8") (pin "TP") (pinfunction "TP_TP") (pintype "input"))
      (node (ref "U1") (pin "6") (pinfunction "CLK_6") (pintype "input"))
      (node (ref "U2") (pin "6") (pinfunction "IO6_6") (pintype "bidirectional"))
    )
    (net (code "45") (name "SCL") (class "Default")
      (node (ref "J3") (pin "4") (pinfunction "4_4") (pintype "passive"))
      (node (ref "R2-PINH") (pin "1") (pinfunction "1_1") (pintype "passive"))
      (node (ref "SENSOR2") (pin "4") (pinfunction "SCK_4") (pintype "input"))
      (node (ref "U2") (pin "20") (pinfunction "IO22_20") (pintype "bidirectional"))
      (node (ref "U3") (pin "16") (pinfunction "SCL_16") (pintype "input"))
      (node (ref "U4") (pin "7") (pinfunction "SCL_7") (pintype "input"))
    )
    (net (code "46") (name "SDA") (class "Default")
      (node (ref "J3") (pin "3") (pinfunction "3_3") (pintype "passive"))
      (node (ref "R1-PINH") (pin "1") (pinfunction "1_1") (pintype "passive"))
      (node (ref "SENSOR2") (pin "3") (pinfunction "SDI_3") (pintype "bidirectional"))
      (node (ref "U2") (pin "19") (pinfunction "IO21_19") (pintype "bidirectional"))
      (node (ref "U3") (pin "15") (pinfunction "SDA_15") (pintype "bidirectional"))
      (node (ref "U4") (pin "8") (pinfunction "SDA_8") (pintype "bidirectional"))
    )
    (net (code "47") (name "SRC") (class "Default")
      (node (ref "C4") (pin "2") (pinfunction "2_2") (pintype "passive"))
      (node (ref "D5") (pin "2") (pinfunction "A_2") (pintype "bidirectional"))
      (node (ref "L1") (pin "1") (pinfunction "1_1") (pintype "passive"))
      (node (ref "Q3") (pin "3") (pinfunction "D_3") (pintype "bidirectional"))
    )
    (net (code "48") (name "SS_SD") (class "Default")
      (node (ref "D8") (pin "2") (pinfunction "2_2") (pintype "passive"))
      (node (ref "J4") (pin "P2") (pinfunction "CD/DAT3_P2") (pintype "bidirectional"))
      (node (ref "R10") (pin "1") (pinfunction "1_1") (pintype "passive"))
      (node (ref "U2") (pin "4") (pinfunction "IO4_4") (pintype "bidirectional"))
    )
    (net (code "49") (name "TX") (class "Default")
      (node (ref "TP1") (pin "TP") (pinfunction "TP_TP") (pintype "input"))
      (node (ref "U2") (pin "25") (pinfunction "TXD0/GPIO16_25") (pintype "bidirectional"))
    )
    (net (code "50") (name "USB_D+") (class "Default")
      (node (ref "D1") (pin "1") (pinfunction "I/O1_1_1") (pintype "bidirectional"))
      (node (ref "U2") (pin "14") (pinfunction "IO13_14") (pintype "bidirectional"))
    )
    (net (code "51") (name "USB_D-") (class "Default")
      (node (ref "D1") (pin "3") (pinfunction "I/O2_1_3") (pintype "bidirectional"))
      (node (ref "U2") (pin "13") (pinfunction "IO12_13") (pintype "bidirectional"))
    )
    (net (code "52") (name "VBAT") (class "Default")
      (node (ref "C2_BAT") (pin "1") (pinfunction "1_1") (pintype "passive"))
      (node (ref "MCP73831") (pin "3") (pinfunction "VBAT_3") (pintype "power_in"))
      (node (ref "Q1") (pin "1") (pinfunction "D_1") (pintype "bidirectional"))
      (node (ref "TP3") (pin "TP") (pinfunction "TP_TP") (pintype "input"))
      (node (ref "U4") (pin "2") (pinfunction "CELL_2") (pintype "power_in"))
      (node (ref "U4") (pin "3") (pinfunction "VDD_3") (pintype "power_in"))
    )
    (net (code "53") (name "VBUS") (class "Default")
      (node (ref "C1_BAT") (pin "1") (pinfunction "1_1") (pintype "passive"))
      (node (ref "C4_USB") (pin "1") (pinfunction "1_1") (pintype "passive"))
      (node (ref "C5_USB") (pin "1") (pinfunction "1_1") (pintype "passive"))
      (node (ref "CHG_LED") (pin "A") (pinfunction "A_A") (pintype "passive"))
      (node (ref "D1") (pin "5") (pinfunction "VBUS_5") (pintype "bidirectional"))
      (node (ref "D2") (pin "1") (pinfunction "ANODE_1") (pintype "bidirectional"))
      (node (ref "MCP73831") (pin "4") (pinfunction "VIN_4") (pintype "power_in"))
      (node (ref "PFMF.050.1") (pin "2") (pinfunction "2_2") (pintype "passive"))
      (node (ref "Q1") (pin "2") (pinfunction "G_2") (pintype "bidirectional"))
      (node (ref "R1_PWRUSB") (pin "2") (pinfunction "2_2") (pintype "passive"))
      (node (ref "TP14") (pin "TP") (pinfunction "TP_TP") (pintype "input"))
    )
    (net (code "54") (name "VRTC") (class "Default")
      (node (ref "C10_SUPERCAP") (pin "2") (pinfunction "2_2") (pintype "passive"))
      (node (ref "C8") (pin "1") (pinfunction "1_1") (pintype "passive"))
      (node (ref "R_CAPACITOR") (pin "1") (pinfunction "1_1") (pintype "passive"))
      (node (ref "U3") (pin "14") (pinfunction "VBAT_14") (pintype "power_in"))
    )
    (net (code "55") (name "VUSB") (class "Default")
      (node (ref "J2") (pin "A4") (pinfunction "A4_A4") (pintype "bidirectional"))
      (node (ref "J2") (pin "A9") (pinfunction "A9_A9") (pintype "bidirectional"))
      (node (ref "J2") (pin "B4") (pinfunction "B4_B4") (pintype "bidirectional"))
      (node (ref "J2") (pin "B9") (pinfunction "B9_B9") (pintype "bidirectional"))
      (node (ref "PFMF.050.1") (pin "1") (pinfunction "1_1") (pintype "passive"))
    )
    (net (code "56") (name "unconnected-(IC1-NC-Pad4)") (class "Default")
      (node (ref "IC1") (pin "4") (pinfunction "NC_4") (pintype "no_connect"))
    )
    (net (code "57") (name "unconnected-(IC4-NC-Pad4)") (class "Default")
      (node (ref "IC4") (pin "4") (pinfunction "NC_4") (pintype "no_connect"))
    )
    (net (code "58") (name "unconnected-(J1-Pad1)") (class "Default")
      (node (ref "J1") (pin "1") (pinfunction "1_1") (pintype "bidirectional"))
    )
    (net (code "59") (name "unconnected-(J1-Pad6)") (class "Default")
      (node (ref "J1") (pin "6") (pinfunction "6_6") (pintype "bidirectional"))
    )
    (net (code "60") (name "unconnected-(J1-Pad7)") (class "Default")
      (node (ref "J1") (pin "7") (pinfunction "7_7") (pintype "bidirectional"))
    )
    (net (code "61") (name "unconnected-(J2-PadA8)") (class "Default")
      (node (ref "J2") (pin "A8") (pinfunction "A8_A8") (pintype "bidirectional"))
    )
    (net (code "62") (name "unconnected-(J2-PadB8)") (class "Default")
      (node (ref "J2") (pin "B8") (pinfunction "B8_B8") (pintype "bidirectional"))
    )
    (net (code "63") (name "unconnected-(J4-DAT1-PadP8)") (class "Default")
      (node (ref "J4") (pin "P8") (pinfunction "DAT1_P8") (pintype "bidirectional"))
    )
    (net (code "64") (name "unconnected-(J4-DAT2-PadP1)") (class "Default")
      (node (ref "J4") (pin "P1") (pinfunction "DAT2_P1") (pintype "bidirectional"))
    )
    (net (code "65") (name "unconnected-(J4-DETECTION_1-PadS1)") (class "Default")
      (node (ref "J4") (pin "S1") (pinfunction "DETECTION_1_S1") (pintype "bidirectional"))
    )
    (net (code "66") (name "unconnected-(J4-DETECTION_2-PadS2)") (class "Default")
      (node (ref "J4") (pin "S2") (pinfunction "DETECTION_2_S2") (pintype "bidirectional"))
    )
    (net (code "67") (name "unconnected-(U2-NC-Pad22)") (class "Default")
      (node (ref "U2") (pin "22") (pinfunction "NC_22") (pintype "no_connect"))
    )
    (net (code "68") (name "unconnected-(U4-~{ALERT}-Pad5)") (class "Default")
      (node (ref "U4") (pin "5") (pinfunction "~{ALERT}_5") (pintype "output"))
    )
  )
)
